# M24C64.net
KiCad netlist of a schematic drawn in EAGLE
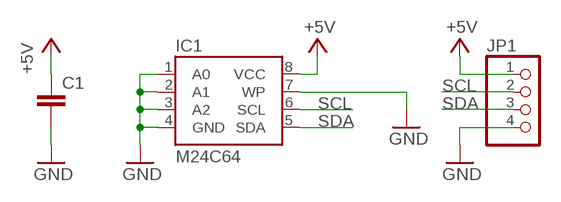
[diagram p0: schematic, sheet 1]

(export (version "E")
  (design (tool "Eeschema 10.0.6"))
  (components
    (comp (ref "C1")
      (value "C-EUC0805K")
      (footprint "eagle-import:C0805K")
      (libsource (lib "eagle-import") (part "C-EUC0805K"))
    )
    (comp (ref "IC1")
      (value "M24C64")
      (footprint "eagle-import:SO08")
      (libsource (lib "eagle-import") (part "AT24C"))
    )
    (comp (ref "JP1")
      (value "PINHD-1X4")
      (footprint "eagle-import:1X04")
      (libsource (lib "eagle-import") (part "PINHD-1X4"))
    )
  )
  (nets
    (net (code "1") (name "+5V") (class "Default")
      (node (ref "C1") (pin "1") (pinfunction "1_1") (pintype "passive"))
      (node (ref "IC1") (pin "8") (pinfunction "VCC_8") (pintype "power_in"))
      (node (ref "JP1") (pin "1") (pinfunction "1_1") (pintype "passive"))
    )
    (net (code "2") (name "/SCL") (class "Default")
      (node (ref "IC1") (pin "6") (pinfunction "SCL_6") (pintype "bidirectional"))
      (node (ref "JP1") (pin "2") (pinfunction "2_2") (pintype "passive"))
    )
    (net (code "3") (name "/SDA") (class "Default")
      (node (ref "IC1") (pin "5") (pinfunction "SDA_5") (pintype "bidirectional"))
      (node (ref "JP1") (pin "3") (pinfunction "3_3") (pintype "passive"))
    )
    (net (code "4") (name "GND") (class "Default")
      (node (ref "C1") (pin "2") (pinfunction "2_2") (pintype "passive"))
      (node (ref "IC1") (pin "1") (pinfunction "A0_1") (pintype "input"))
      (node (ref "IC1") (pin "2") (pinfunction "A1_2") (pintype "input"))
      (node (ref "IC1") (pin "3") (pinfunction "A2_3") (pintype "input"))
      (node (ref "IC1") (pin "4") (pinfunction "GND_4") (pintype "power_in"))
      (node (ref "IC1") (pin "7") (pinfunction "WP_7") (pintype "input"))
      (node (ref "JP1") (pin "4") (pinfunction "4_4") (pintype "passive"))
    )
  )
)
